# SCH___2022-03-10.net
KiCad netlist of a schematic drawn in EasyEDA
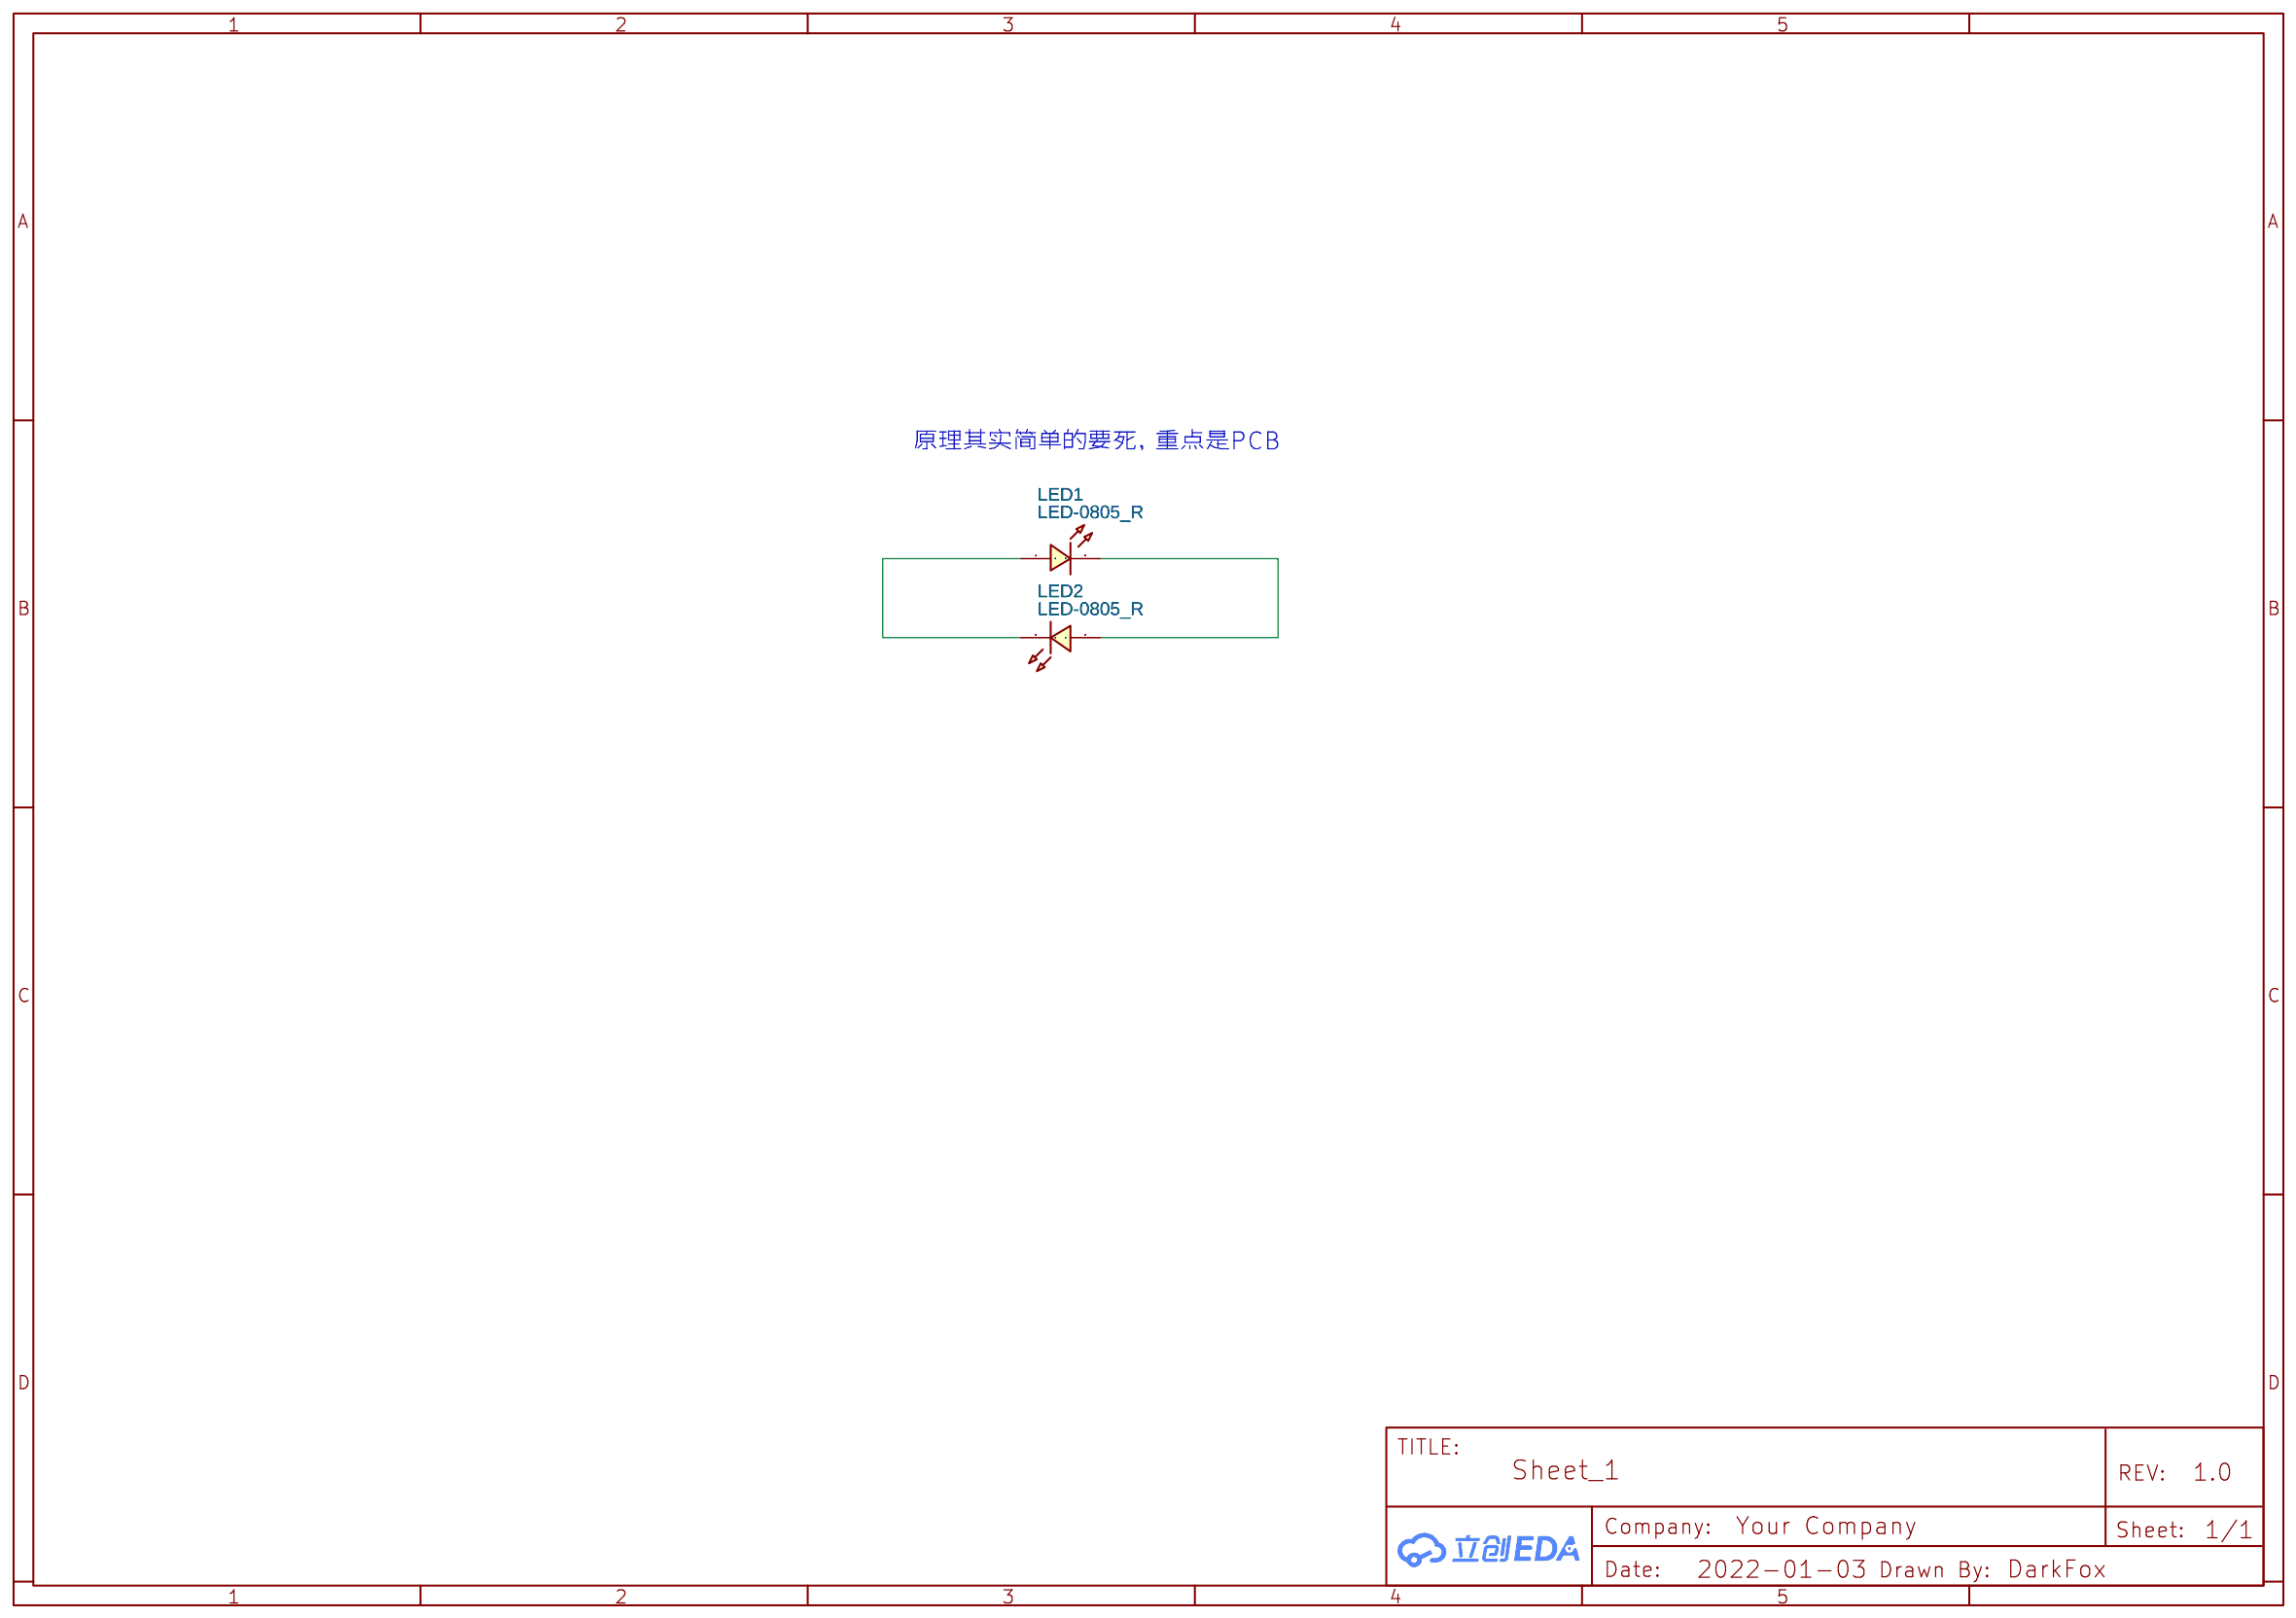
[diagram p0: schematic sheet]

(export (version "E")
  (design (tool "Eeschema 10.0.6"))
  (components
    (comp (ref "LED1")
      (value "LED-0805_R")
      (fields
        (field (name "BOM_Manufacturer Part") "17-21SURC/S530-A3/TR8")
        (field (name "BOM_Supplier Part") "C72037")
      )
      (libsource (lib "") (part "LED-0805_R_1"))
    )
    (comp (ref "LED2")
      (value "LED-0805_R")
      (fields
        (field (name "BOM_Manufacturer Part") "17-21SURC/S530-A3/TR8")
        (field (name "BOM_Supplier Part") "C72037")
      )
      (libsource (lib "") (part "LED-0805_R"))
    )
  )
  (nets
    (net (code "1") (name "Net-(LED1-Pad1)") (class "Default")
      (node (ref "LED1") (pin "1") (pinfunction "1_1") (pintype "unspecified"))
      (node (ref "LED2") (pin "2") (pinfunction "2_2") (pintype "unspecified"))
    )
    (net (code "2") (name "Net-(LED1-Pad2)") (class "Default")
      (node (ref "LED1") (pin "2") (pinfunction "2_2") (pintype "unspecified"))
      (node (ref "LED2") (pin "1") (pinfunction "1_1") (pintype "unspecified"))
    )
  )
)
